# Lamp_Segment.net
KiCad netlist of a schematic drawn in EAGLE
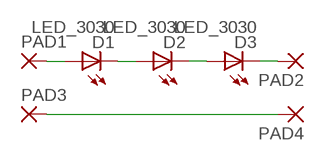
[diagram p0: schematic, sheet 1]

(export (version "E")
  (design (tool "Eeschema 10.0.6"))
  (components
    (comp (ref "D1")
      (value "LED_3030")
      (footprint "eagle-import:LED3030")
      (libsource (lib "eagle-import") (part "LED_3030"))
    )
    (comp (ref "D2")
      (value "LED_3030")
      (footprint "eagle-import:LED3030")
      (libsource (lib "eagle-import") (part "LED_3030"))
    )
    (comp (ref "D3")
      (value "LED_3030")
      (footprint "eagle-import:LED3030")
      (libsource (lib "eagle-import") (part "LED_3030"))
    )
    (comp (ref "PAD1")
      (value "SMD5")
      (footprint "eagle-import:SMD2,54-5,08")
      (libsource (lib "eagle-import") (part "SMD5"))
    )
    (comp (ref "PAD2")
      (value "SMD5")
      (footprint "eagle-import:SMD2,54-5,08")
      (libsource (lib "eagle-import") (part "SMD5"))
    )
    (comp (ref "PAD3")
      (value "SMD5")
      (footprint "eagle-import:SMD2,54-5,08")
      (libsource (lib "eagle-import") (part "SMD5"))
    )
    (comp (ref "PAD4")
      (value "SMD5")
      (footprint "eagle-import:SMD2,54-5,08")
      (libsource (lib "eagle-import") (part "SMD5"))
    )
  )
  (nets
    (net (code "1") (name "Net-(D1-A)") (class "Default")
      (node (ref "D1") (pin "P$1") (pinfunction "A_P$1") (pintype "passive"))
      (node (ref "PAD1") (pin "1") (pinfunction "P_1") (pintype "passive"))
    )
    (net (code "2") (name "Net-(D1-C)") (class "Default")
      (node (ref "D1") (pin "P$2") (pinfunction "C_P$2") (pintype "passive"))
      (node (ref "D2") (pin "P$1") (pinfunction "A_P$1") (pintype "passive"))
    )
    (net (code "3") (name "Net-(D2-C)") (class "Default")
      (node (ref "D2") (pin "P$2") (pinfunction "C_P$2") (pintype "passive"))
      (node (ref "D3") (pin "P$1") (pinfunction "A_P$1") (pintype "passive"))
    )
    (net (code "4") (name "Net-(D3-C)") (class "Default")
      (node (ref "D3") (pin "P$2") (pinfunction "C_P$2") (pintype "passive"))
      (node (ref "PAD2") (pin "1") (pinfunction "P_1") (pintype "passive"))
    )
    (net (code "5") (name "Net-(PAD3-P)") (class "Default")
      (node (ref "PAD3") (pin "1") (pinfunction "P_1") (pintype "passive"))
      (node (ref "PAD4") (pin "1") (pinfunction "P_1") (pintype "passive"))
    )
  )
)
